# EagleSchematicv2.net
KiCad netlist of a schematic drawn in EAGLE
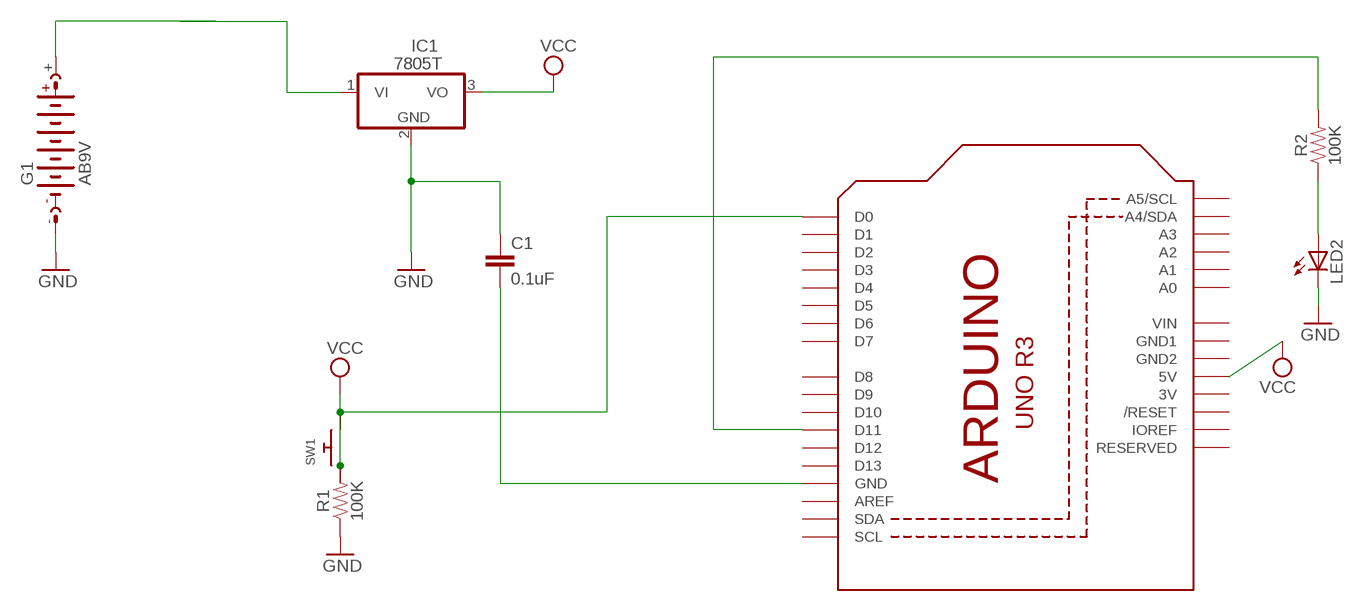
[diagram p0: schematic, sheet 1]

(export (version "E")
  (design (tool "Eeschema 10.0.6"))
  (components
    (comp (ref "C1")
      (value "0.1uF")
      (footprint "eagle-import:0402")
      (libsource (lib "eagle-import") (part "0.1UF-0402-16V-10%"))
    )
    (comp (ref "G1")
      (value "AB9V")
      (footprint "eagle-import:AB9V")
      (libsource (lib "eagle-import") (part "AB9V"))
    )
    (comp (ref "IC1")
      (value "7805T")
      (footprint "eagle-import:TO220H")
      (libsource (lib "eagle-import") (part "78T05"))
    )
    (comp (ref "LED2")
      (value "LED5MM")
      (footprint "eagle-import:LED5MM")
      (libsource (lib "eagle-import") (part "LED5MM"))
    )
    (comp (ref "R1")
      (value "100K")
      (footprint "eagle-import:0402")
      (libsource (lib "eagle-import") (part "100KOHM-0402-1/16W-1%"))
    )
    (comp (ref "R2")
      (value "100K")
      (footprint "eagle-import:0402")
      (libsource (lib "eagle-import") (part "100KOHM-0402-1/16W-1%"))
    )
    (comp (ref "SW1")
      (value "SWITCH_PUSHBUTTONSOFTTOUCHSMD_SJ")
      (footprint "eagle-import:PUSHBUTTON_SMD_SJ")
      (libsource (lib "eagle-import") (part "SWITCH_PUSHBUTTONSOFTTOUCHSMD_SJ"))
    )
    (comp (ref "U1")
      (value "ARDUINOR3-BPLACE")
      (footprint "eagle-import:ARDUINOR3-BPLACE")
      (libsource (lib "eagle-import") (part "ARDUINOR3-BPLACE"))
    )
  )
  (nets
    (net (code "1") (name "/3V") (class "Default")
      (node (ref "U1") (pin "3V") (pinfunction "3V_3V") (pintype "power_in"))
    )
    (net (code "2") (name "/GND1") (class "Default")
      (node (ref "U1") (pin "GND1") (pinfunction "GND1_GND1") (pintype "power_in"))
    )
    (net (code "3") (name "/GND2") (class "Default")
      (node (ref "U1") (pin "GND2") (pinfunction "GND2_GND2") (pintype "power_in"))
    )
    (net (code "4") (name "/VIN") (class "Default")
      (node (ref "U1") (pin "VIN") (pinfunction "VIN_VIN") (pintype "power_in"))
    )
    (net (code "5") (name "GND") (class "Default")
      (node (ref "C1") (pin "1") (pinfunction "1_1") (pintype "passive"))
      (node (ref "G1") (pin "-") (pinfunction "-_-") (pintype "passive"))
      (node (ref "IC1") (pin "2") (pinfunction "GND_2") (pintype "passive"))
      (node (ref "LED2") (pin "K") (pinfunction "C_K") (pintype "passive"))
      (node (ref "R1") (pin "1") (pinfunction "1_1") (pintype "passive"))
    )
    (net (code "6") (name "Net-(C1-Pad2)") (class "Default")
      (node (ref "C1") (pin "2") (pinfunction "2_2") (pintype "passive"))
      (node (ref "U1") (pin "GND") (pinfunction "GND_GND") (pintype "power_in"))
    )
    (net (code "7") (name "Net-(LED2-PadA)") (class "Default")
      (node (ref "LED2") (pin "A") (pinfunction "A_A") (pintype "passive"))
      (node (ref "R2") (pin "1") (pinfunction "1_1") (pintype "passive"))
    )
    (net (code "8") (name "Net-(R2-Pad2)") (class "Default")
      (node (ref "R2") (pin "2") (pinfunction "2_2") (pintype "passive"))
      (node (ref "U1") (pin "D11") (pinfunction "D11_D11") (pintype "bidirectional"))
    )
    (net (code "9") (name "VCC") (class "Default")
      (node (ref "IC1") (pin "3") (pinfunction "VO_3") (pintype "passive"))
      (node (ref "R1") (pin "2") (pinfunction "2_2") (pintype "passive"))
      (node (ref "SW1") (pin "P$2") (pinfunction "P$2_P$2") (pintype "passive"))
      (node (ref "U1") (pin "5V") (pinfunction "5V_5V") (pintype "power_in"))
      (node (ref "U1") (pin "D0") (pinfunction "D0_D0") (pintype "bidirectional"))
    )
    (net (code "10") (name "unconnected-(G1-Pad+)") (class "Default")
      (node (ref "G1") (pin "+") (pinfunction "+_+") (pintype "passive"))
    )
    (net (code "11") (name "unconnected-(IC1-VI-Pad1)") (class "Default")
      (node (ref "IC1") (pin "1") (pinfunction "VI_1") (pintype "input"))
    )
    (net (code "12") (name "unconnected-(SW1-PadP$1)") (class "Default")
      (node (ref "SW1") (pin "P$1") (pinfunction "P$1_P$1") (pintype "passive"))
    )
    (net (code "13") (name "unconnected-(U1-A4{slash}SDA-PadA4)") (class "Default")
      (node (ref "U1") (pin "A4") (pinfunction "A4/SDA_A4") (pintype "bidirectional"))
    )
    (net (code "14") (name "unconnected-(U1-A5{slash}SCL-PadA5)") (class "Default")
      (node (ref "U1") (pin "A5") (pinfunction "A5/SCL_A5") (pintype "bidirectional"))
    )
    (net (code "15") (name "unconnected-(U1-PadA0)") (class "Default")
      (node (ref "U1") (pin "A0") (pinfunction "A0_A0") (pintype "bidirectional"))
    )
    (net (code "16") (name "unconnected-(U1-PadA1)") (class "Default")
      (node (ref "U1") (pin "A1") (pinfunction "A1_A1") (pintype "bidirectional"))
    )
    (net (code "17") (name "unconnected-(U1-PadA2)") (class "Default")
      (node (ref "U1") (pin "A2") (pinfunction "A2_A2") (pintype "bidirectional"))
    )
    (net (code "18") (name "unconnected-(U1-PadA3)") (class "Default")
      (node (ref "U1") (pin "A3") (pinfunction "A3_A3") (pintype "bidirectional"))
    )
    (net (code "19") (name "unconnected-(U1-PadAREF)") (class "Default")
      (node (ref "U1") (pin "AREF") (pinfunction "AREF_AREF") (pintype "bidirectional"))
    )
    (net (code "20") (name "unconnected-(U1-PadD1)") (class "Default")
      (node (ref "U1") (pin "D1") (pinfunction "D1_D1") (pintype "bidirectional"))
    )
    (net (code "21") (name "unconnected-(U1-PadD2)") (class "Default")
      (node (ref "U1") (pin "D2") (pinfunction "D2_D2") (pintype "bidirectional"))
    )
    (net (code "22") (name "unconnected-(U1-PadD3)") (class "Default")
      (node (ref "U1") (pin "D3") (pinfunction "D3_D3") (pintype "bidirectional"))
    )
    (net (code "23") (name "unconnected-(U1-PadD4)") (class "Default")
      (node (ref "U1") (pin "D4") (pinfunction "D4_D4") (pintype "bidirectional"))
    )
    (net (code "24") (name "unconnected-(U1-PadD5)") (class "Default")
      (node (ref "U1") (pin "D5") (pinfunction "D5_D5") (pintype "bidirectional"))
    )
    (net (code "25") (name "unconnected-(U1-PadD6)") (class "Default")
      (node (ref "U1") (pin "D6") (pinfunction "D6_D6") (pintype "bidirectional"))
    )
    (net (code "26") (name "unconnected-(U1-PadD7)") (class "Default")
      (node (ref "U1") (pin "D7") (pinfunction "D7_D7") (pintype "bidirectional"))
    )
    (net (code "27") (name "unconnected-(U1-PadD8)") (class "Default")
      (node (ref "U1") (pin "D8") (pinfunction "D8_D8") (pintype "bidirectional"))
    )
    (net (code "28") (name "unconnected-(U1-PadD9)") (class "Default")
      (node (ref "U1") (pin "D9") (pinfunction "D9_D9") (pintype "bidirectional"))
    )
    (net (code "29") (name "unconnected-(U1-PadD10)") (class "Default")
      (node (ref "U1") (pin "D10") (pinfunction "D10_D10") (pintype "bidirectional"))
    )
    (net (code "30") (name "unconnected-(U1-PadD12)") (class "Default")
      (node (ref "U1") (pin "D12") (pinfunction "D12_D12") (pintype "bidirectional"))
    )
    (net (code "31") (name "unconnected-(U1-PadD13)") (class "Default")
      (node (ref "U1") (pin "D13") (pinfunction "D13_D13") (pintype "bidirectional"))
    )
    (net (code "32") (name "unconnected-(U1-PadIOREF)") (class "Default")
      (node (ref "U1") (pin "IOREF") (pinfunction "IOREF_IOREF") (pintype "output"))
    )
    (net (code "33") (name "unconnected-(U1-PadRESERVED)") (class "Default")
      (node (ref "U1") (pin "RESERVED") (pinfunction "RESERVED_RESERVED") (pintype "no_connect"))
    )
    (net (code "34") (name "unconnected-(U1-PadSCL)") (class "Default")
      (node (ref "U1") (pin "SCL") (pinfunction "SCL_SCL") (pintype "bidirectional"))
    )
    (net (code "35") (name "unconnected-(U1-PadSDA)") (class "Default")
      (node (ref "U1") (pin "SDA") (pinfunction "SDA_SDA") (pintype "bidirectional"))
    )
    (net (code "36") (name "unconnected-(U1-{slash}RESET-PadRESET)") (class "Default")
      (node (ref "U1") (pin "RESET") (pinfunction "/RESET_RESET") (pintype "bidirectional"))
    )
  )
)
